# Stepper_Driver_Design.net
KiCad netlist of a schematic drawn in EAGLE
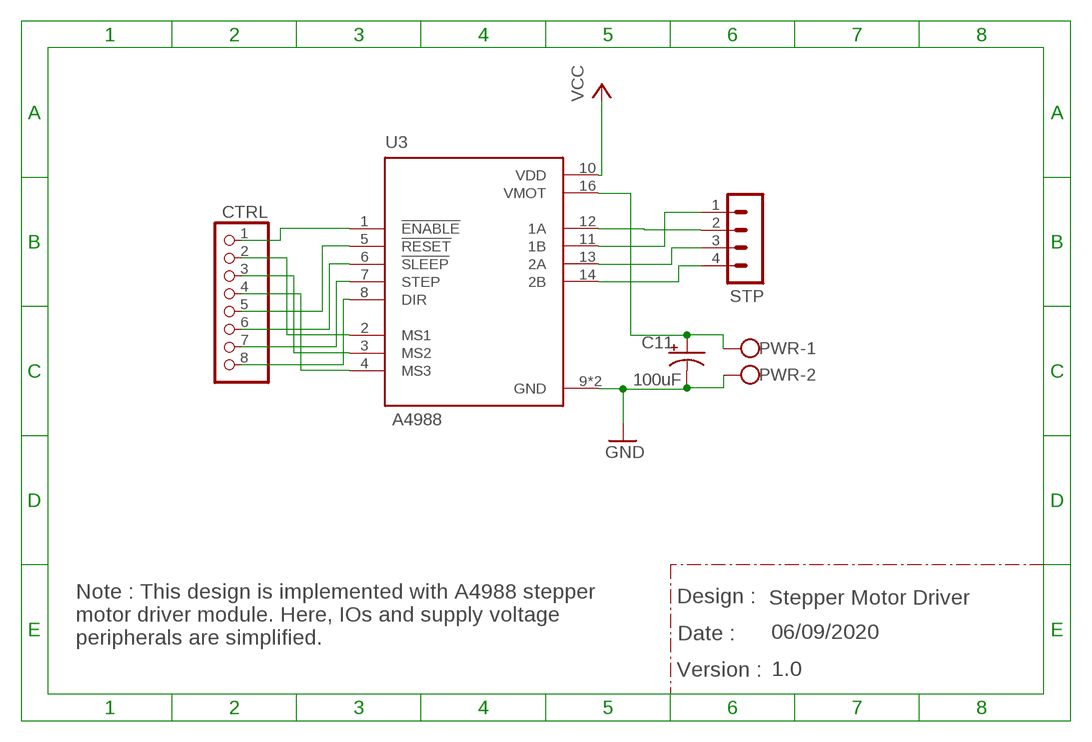
[diagram p0: schematic, sheet 1]

(export (version "E")
  (design (tool "Eeschema 10.0.6"))
  (components
    (comp (ref "C11")
      (value "100uF")
      (footprint "eagle-import:140CLH-1010")
      (libsource (lib "eagle-import") (part "CPOL-US140CLH-1010"))
    )
    (comp (ref "CTRL")
      (value "PINHD-1X8BIG")
      (footprint "eagle-import:1X08-BIG")
      (libsource (lib "eagle-import") (part "PINHD-1X8BIG"))
    )
    (comp (ref "PWR")
      (value "W237-102")
      (footprint "eagle-import:W237-102")
      (fields (field (name "MPN") "237-102"))
      (libsource (lib "eagle-import") (part "W237-102"))
    )
    (comp (ref "STP")
      (value "MA04-1")
      (footprint "eagle-import:MA04-1")
      (libsource (lib "eagle-import") (part "MA04-1"))
    )
    (comp (ref "U3")
      (value "A4988")
      (footprint "eagle-import:MODULE_A4988_STEPPER_MOTOR_DRIVER_CARRIER")
      (fields (field (name "MF") "Pololu") (field (name "MP") "A4988 STEPPER MOTOR DRIVER CARRIER"))
      (libsource (lib "eagle-import") (part "A4988_STEPPER_MOTOR_DRIVER_CARRIER"))
    )
  )
  (nets
    (net (code "1") (name "GND") (class "Default")
      (node (ref "C11") (pin "-") (pinfunction "-_-") (pintype "passive"))
      (node (ref "PWR") (pin "2") (pinfunction "KL_2") (pintype "passive"))
      (node (ref "U3") (pin "15") (pinfunction "GND_15") (pintype "power_in"))
      (node (ref "U3") (pin "9") (pinfunction "GND_9") (pintype "power_in"))
    )
    (net (code "2") (name "Net-(PWRA-KL)") (class "Default")
      (node (ref "C11") (pin "+") (pinfunction "+_+") (pintype "passive"))
      (node (ref "PWR") (pin "1") (pinfunction "KL_1") (pintype "passive"))
      (node (ref "U3") (pin "16") (pinfunction "VMOT_16") (pintype "power_in"))
    )
    (net (code "3") (name "Net-(U3-1A)") (class "Default")
      (node (ref "STP") (pin "2") (pinfunction "2_2") (pintype "passive"))
      (node (ref "U3") (pin "12") (pinfunction "1A_12") (pintype "output"))
    )
    (net (code "4") (name "Net-(U3-1B)") (class "Default")
      (node (ref "STP") (pin "1") (pinfunction "1_1") (pintype "passive"))
      (node (ref "U3") (pin "11") (pinfunction "1B_11") (pintype "output"))
    )
    (net (code "5") (name "Net-(U3-2A)") (class "Default")
      (node (ref "STP") (pin "3") (pinfunction "3_3") (pintype "passive"))
      (node (ref "U3") (pin "13") (pinfunction "2A_13") (pintype "output"))
    )
    (net (code "6") (name "Net-(U3-2B)") (class "Default")
      (node (ref "STP") (pin "4") (pinfunction "4_4") (pintype "passive"))
      (node (ref "U3") (pin "14") (pinfunction "2B_14") (pintype "output"))
    )
    (net (code "7") (name "Net-(U3-DIR)") (class "Default")
      (node (ref "CTRL") (pin "8") (pinfunction "8_8") (pintype "passive"))
      (node (ref "U3") (pin "8") (pinfunction "DIR_8") (pintype "input"))
    )
    (net (code "8") (name "Net-(U3-MS1)") (class "Default")
      (node (ref "CTRL") (pin "2") (pinfunction "2_2") (pintype "passive"))
      (node (ref "U3") (pin "2") (pinfunction "MS1_2") (pintype "input"))
    )
    (net (code "9") (name "Net-(U3-MS2)") (class "Default")
      (node (ref "CTRL") (pin "3") (pinfunction "3_3") (pintype "passive"))
      (node (ref "U3") (pin "3") (pinfunction "MS2_3") (pintype "input"))
    )
    (net (code "10") (name "Net-(U3-MS3)") (class "Default")
      (node (ref "CTRL") (pin "4") (pinfunction "4_4") (pintype "passive"))
      (node (ref "U3") (pin "4") (pinfunction "MS3_4") (pintype "input"))
    )
    (net (code "11") (name "Net-(U3-STEP)") (class "Default")
      (node (ref "CTRL") (pin "7") (pinfunction "7_7") (pintype "passive"))
      (node (ref "U3") (pin "7") (pinfunction "STEP_7") (pintype "input"))
    )
    (net (code "12") (name "Net-(U3-~{ENABLE})") (class "Default")
      (node (ref "CTRL") (pin "1") (pinfunction "1_1") (pintype "passive"))
      (node (ref "U3") (pin "1") (pinfunction "~{ENABLE}_1") (pintype "input"))
    )
    (net (code "13") (name "Net-(U3-~{RESET})") (class "Default")
      (node (ref "CTRL") (pin "5") (pinfunction "5_5") (pintype "passive"))
      (node (ref "U3") (pin "5") (pinfunction "~{RESET}_5") (pintype "input"))
    )
    (net (code "14") (name "Net-(U3-~{SLEEP})") (class "Default")
      (node (ref "CTRL") (pin "6") (pinfunction "6_6") (pintype "passive"))
      (node (ref "U3") (pin "6") (pinfunction "~{SLEEP}_6") (pintype "input"))
    )
    (net (code "15") (name "VCC") (class "Default")
      (node (ref "U3") (pin "10") (pinfunction "VDD_10") (pintype "power_in"))
    )
  )
)
